# Sheet1.net
KiCad netlist of a schematic drawn in Altium Designer
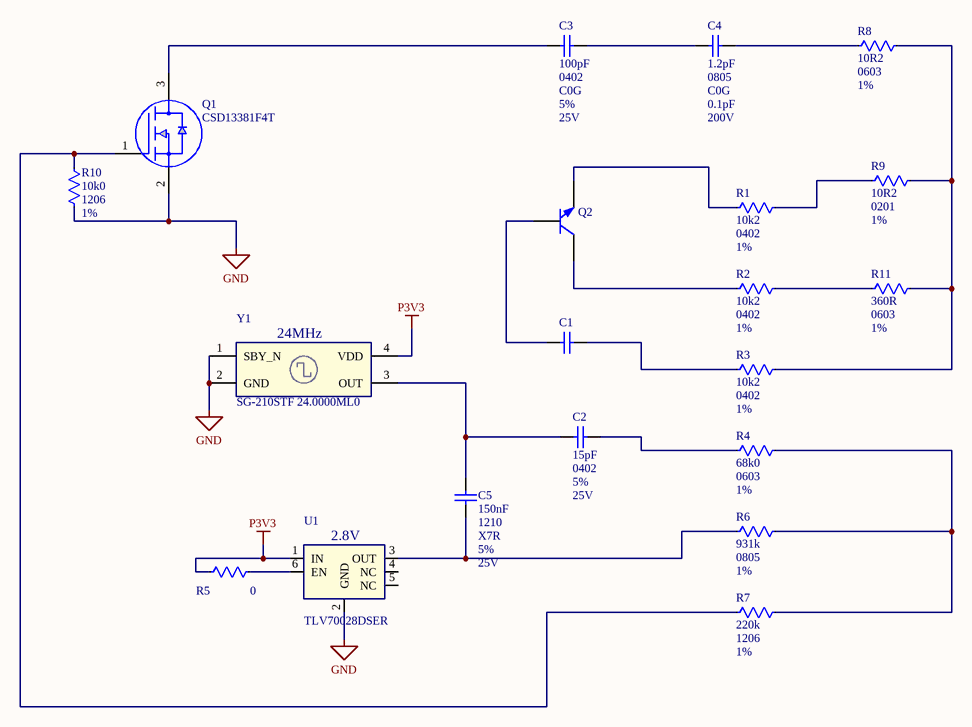
[diagram p0: Sheet1.SchDoc]

(export (version "E")
  (design (tool "Eeschema 10.0.6"))
  (components
    (comp (ref "C1")
      (value "100pF")
      (footprint "CAPC_0201(0603)_P33_N")
      (fields
        (field (name "MFR PART NUMBER") "C0201C101J3GACTU")
        (field (name "MANUFACTURER") "KEMET")
        (field (name "TOLERANCE") "±5%")
        (field (name "CREATED BY") "KristinPollock")
        (field (name "CHECKED BY") "KristinPollock")
        (field (name "UPDATED BY") "KristinPollock")
      )
      (libsource (lib "Parts") (part "CAP"))
    )
    (comp (ref "C2")
      (value "15pF")
      (footprint "CAPC_0402(1005)_P55_N")
      (description "Cap, Cer, 15pF, 5%, 25V, 0402, C0G")
      (fields
        (field (name "PACKAGE_CASE") "0402")
        (field (name "TOLERANCE") "5%")
        (field (name "VOLTAGE_RATING") "25V")
        (field (name "MFR PART NUMBER") "04023A150JAT")
        (field (name "MANUFACTURER") "AVX")
        (field (name "CREATED BY") "DJH Script")
        (field (name "CHECKED BY") "DJH Script")
      )
      (libsource (lib "passives") (part "CAPDB"))
    )
    (comp (ref "C3")
      (value "100pF")
      (footprint "CAPC_0402(1005)_P55_N")
      (description "Cap, Cer, 100pF, 5%, 25V, 0402, C0G")
      (fields
        (field (name "PACKAGE_CASE") "0402")
        (field (name "DIELECTRIC") "C0G")
        (field (name "TOLERANCE") "5%")
        (field (name "VOLTAGE_RATING") "25V")
        (field (name "MFR PART NUMBER") "04023A101JAT")
        (field (name "MANUFACTURER") "AVX")
        (field (name "CREATED BY") "DJH Script")
        (field (name "CHECKED BY") "DJH Script")
      )
      (libsource (lib "passives") (part "CAPDB"))
    )
    (comp (ref "C4")
      (value "1.2pF")
      (footprint "CAPC_0805(2012)_P95_N")
      (description "Cap, Cer, 1.2pF, 0.1pF, 200V, 0805, C0G")
      (fields
        (field (name "PACKAGE_CASE") "0805")
        (field (name "DIELECTRIC") "C0G")
        (field (name "TOLERANCE") "0.1pF")
        (field (name "VOLTAGE_RATING") "200V")
        (field (name "MFR PART NUMBER") "08052A1R2BAT")
        (field (name "MANUFACTURER") "AVX")
        (field (name "CREATED BY") "DJH Script")
        (field (name "CHECKED BY") "DJH Script")
      )
      (libsource (lib "passives") (part "CAPDB"))
    )
    (comp (ref "C5")
      (value "150nF")
      (footprint "CAPC_1210(3225)_P9_L")
      (description "Cap, Cer, 150nF, 5%, 25V, 1210, X7R")
      (fields
        (field (name "PACKAGE_CASE") "1210")
        (field (name "DIELECTRIC") "X7R")
        (field (name "TOLERANCE") "5%")
        (field (name "VOLTAGE_RATING") "25V")
        (field (name "MFR PART NUMBER") "12103C154JAT")
        (field (name "MANUFACTURER") "AVX")
        (field (name "CREATED BY") "DJH Script")
        (field (name "CHECKED BY") "DJH Script")
      )
      (libsource (lib "passives") (part "CAPDB"))
    )
    (comp (ref "Q1")
      (value "CSD13381F4T")
      (footprint "MOSFET3_TI_CSD13381F4T")
      (description "MOSFET N-CH 12V 2.1A 3PICOSTAR")
      (fields
        (field (name "MFG") "TI")
        (field (name "MANUFACTURER") "Texas Instruments")
        (field (name "CREATED BY") "Kristin Pollock")
        (field (name "CHECKED BY") "Kristin Pollock")
        (field (name "UPDATED BY") "Kristin Pollock")
      )
      (libsource (lib "Parts") (part "FET N-CH CSD13381F4T"))
    )
    (comp (ref "Q2")
      (value "MMBT3904-7-F")
      (footprint "SOT-23")
      (description "NPN General Purpose Amplifier")
      (fields
        (field (name "MFG") "Diodes Inc")
        (field (name "MANUFACTURER") "Diodes Incorporated")
        (field (name "CREATED BY") "DaveHough")
        (field (name "CHECKED BY") "DaveHough")
        (field (name "UPDATED BY") "DaveHough")
      )
      (libsource (lib "Parts") (part "MMBT3904-7-F"))
    )
    (comp (ref "R1")
      (value "10k2")
      (footprint "RESC_0402(1005)_P4_N")
      (description "Res 0402 1% 10k2 1/16W")
      (fields
        (field (name "PACKAGE_CASE") "0402")
        (field (name "TOLERANCE") "1%")
        (field (name "MFR PART NUMBER") "ERJ2RKF1022X")
        (field (name "MANUFACTURER") "Panasonic")
        (field (name "CREATED BY") "DJH Script")
        (field (name "CHECKED BY") "DJH Script")
      )
      (libsource (lib "passives") (part "RES"))
    )
    (comp (ref "R2")
      (value "10k2")
      (footprint "RESC_0402(1005)_P4_N")
      (description "Res 0402 1% 10k2 1/16W")
      (fields
        (field (name "PACKAGE_CASE") "0402")
        (field (name "TOLERANCE") "1%")
        (field (name "MFR PART NUMBER") "ERJ2RKF1022X")
        (field (name "MANUFACTURER") "Panasonic")
        (field (name "CREATED BY") "DJH Script")
        (field (name "CHECKED BY") "DJH Script")
      )
      (libsource (lib "passives") (part "RES"))
    )
    (comp (ref "R3")
      (value "10k2")
      (footprint "RESC_0402(1005)_P4_N")
      (description "Res 0402 1% 10k2 1/16W")
      (fields
        (field (name "PACKAGE_CASE") "0402")
        (field (name "TOLERANCE") "1%")
        (field (name "MFR PART NUMBER") "ERJ2RKF1022X")
        (field (name "MANUFACTURER") "Panasonic")
        (field (name "CREATED BY") "DJH Script")
        (field (name "CHECKED BY") "DJH Script")
      )
      (libsource (lib "passives") (part "RES"))
    )
    (comp (ref "R4")
      (value "68k0")
      (footprint "RESC_0603(1608)_P55_N")
      (description "Res 0603 1% 68k0 1/10W")
      (fields
        (field (name "PACKAGE_CASE") "0603")
        (field (name "TOLERANCE") "1%")
        (field (name "MFR PART NUMBER") "ERJ3EKF6802V")
        (field (name "MANUFACTURER") "Panasonic")
        (field (name "CREATED BY") "DJH Script")
        (field (name "CHECKED BY") "DJH Script")
      )
      (libsource (lib "passives") (part "RES"))
    )
    (comp (ref "R5")
      (value "0")
      (footprint "RESC_0603(1608)_P55_N")
      (fields
        (field (name "MFR PART NUMBER") "RC0603JR-070RL")
        (field (name "MANUFACTURER") "Yageo")
        (field (name "TOLERANCE") "Jumper")
        (field (name "CREATED BY") "Kristin Pollock")
        (field (name "CHECKED BY") "Kristin Pollock")
        (field (name "UPDATED BY") "KristinPollock")
      )
      (libsource (lib "Parts") (part "RES"))
    )
    (comp (ref "R6")
      (value "931k")
      (footprint "RESC_0805(2012)_P6_N")
      (description "Res 0805 1% 931k 1/8W")
      (fields
        (field (name "PACKAGE_CASE") "0805")
        (field (name "TOLERANCE") "1%")
        (field (name "MFR PART NUMBER") "ERJ6ENF9313V")
        (field (name "MANUFACTURER") "Panasonic")
        (field (name "CREATED BY") "DJH Script")
        (field (name "CHECKED BY") "DJH Script")
      )
      (libsource (lib "passives") (part "RES"))
    )
    (comp (ref "R7")
      (value "220k")
      (footprint "RESC_1206(3216)_P6_N")
      (description "Res 1206 1% 220k 1/4W")
      (fields
        (field (name "PACKAGE_CASE") "1206")
        (field (name "TOLERANCE") "1%")
        (field (name "MFR PART NUMBER") "ERJ8ENF2203V")
        (field (name "MANUFACTURER") "Panasonic")
        (field (name "CREATED BY") "DJH Script")
        (field (name "CHECKED BY") "DJH Script")
      )
      (libsource (lib "passives") (part "RES"))
    )
    (comp (ref "R8")
      (value "10R2")
      (footprint "RESC_0603(1608)_P55_N")
      (description "Res 0603 1% 10R2 1/10W")
      (fields
        (field (name "PACKAGE_CASE") "0603")
        (field (name "TOLERANCE") "1%")
        (field (name "MFR PART NUMBER") "ERJ3EKF10R2V")
        (field (name "MANUFACTURER") "Panasonic")
        (field (name "CREATED BY") "DJH Script")
        (field (name "CHECKED BY") "DJH Script")
      )
      (libsource (lib "passives") (part "RES"))
    )
    (comp (ref "R9")
      (value "10R2")
      (footprint "RESC_0201(0603)_P28_N")
      (description "Res 0201 1% 10R2 1/20W")
      (fields
        (field (name "PACKAGE_CASE") "0201")
        (field (name "TOLERANCE") "1%")
        (field (name "MFR PART NUMBER") "ERJ1GNF10R2C")
        (field (name "MANUFACTURER") "Panasonic")
        (field (name "CREATED BY") "DJH Script")
        (field (name "CHECKED BY") "DJH Script")
      )
      (libsource (lib "passives") (part "RES"))
    )
    (comp (ref "R10")
      (value "10k0")
      (footprint "RESC_1206(3216)_P6_N")
      (description "Res 1206 1% 10k0 1/4W")
      (fields
        (field (name "PACKAGE_CASE") "1206")
        (field (name "TOLERANCE") "1%")
        (field (name "MFR PART NUMBER") "ERJ8ENF1002V")
        (field (name "MANUFACTURER") "Panasonic")
        (field (name "CREATED BY") "DJH Script")
        (field (name "CHECKED BY") "DJH Script")
      )
      (libsource (lib "passives") (part "RES"))
    )
    (comp (ref "R11")
      (value "360R")
      (footprint "RESC_0603(1608)_P55_N")
      (description "Res 0603 1% 360R 1/10W")
      (fields
        (field (name "PACKAGE_CASE") "0603")
        (field (name "TOLERANCE") "1%")
        (field (name "MFR PART NUMBER") "ERJ3EKF3600V")
        (field (name "MANUFACTURER") "Panasonic")
        (field (name "CREATED BY") "DJH Script")
        (field (name "CHECKED BY") "DJH Script")
      )
      (libsource (lib "passives") (part "RES"))
    )
    (comp (ref "U1")
      (value "TLV70028DSER")
      (footprint "TI DSE S-PWSON-N6")
      (description "IC REG LDO 2.8V 0.2A 6WSON")
      (fields
        (field (name "MFG") "TI")
        (field (name "MANUFACTURER") "Texas Instruments")
        (field (name "CREATED BY") "Kristin Pollock")
        (field (name "CHECKED BY") "Kristin Pollock")
        (field (name "UPDATED BY") "Kristin Pollock")
      )
      (libsource (lib "Parts") (part "TLV70028DSER"))
    )
    (comp (ref "Y1")
      (value "SG-210STF 24.0000ML0")
      (footprint "Epson SG-210STF")
      (description "OSC XO 24.000MHZ CMOS SMD")
      (fields
        (field (name "MFG") "Abracon")
        (field (name "MANUFACTURER") "EPSON")
        (field (name "CREATED BY") "Kristin Pollock")
        (field (name "CHECKED BY") "Kristin Pollock")
        (field (name "UPDATED BY") "Kristin Pollock")
      )
      (libsource (lib "Parts") (part "SG-210STF 24.0000ML0"))
    )
  )
  (nets
    (net (code "1") (name "GND") (class "Default")
      (node (ref "Q1") (pin "2") (pinfunction "S_2") (pintype "passive"))
      (node (ref "R10") (pin "2") (pintype "passive"))
      (node (ref "U1") (pin "2") (pinfunction "GND_2") (pintype "passive"))
      (node (ref "Y1") (pin "1") (pinfunction "SBY_N_1") (pintype "passive"))
      (node (ref "Y1") (pin "2") (pinfunction "GND_2") (pintype "passive"))
    )
    (net (code "2") (name "Net-(C1-Pad2)") (class "Default")
      (node (ref "C1") (pin "2") (pinfunction "2_2") (pintype "passive"))
      (node (ref "R3") (pin "2") (pintype "passive"))
    )
    (net (code "3") (name "Net-(C2-Pad2)") (class "Default")
      (node (ref "C2") (pin "2") (pinfunction "2_2") (pintype "passive"))
      (node (ref "R4") (pin "2") (pintype "passive"))
    )
    (net (code "4") (name "Net-(C3-Pad2)") (class "Default")
      (node (ref "C3") (pin "2") (pinfunction "2_2") (pintype "passive"))
      (node (ref "C4") (pin "1") (pinfunction "1_1") (pintype "passive"))
    )
    (net (code "5") (name "Net-(C4-Pad2)") (class "Default")
      (node (ref "C4") (pin "2") (pinfunction "2_2") (pintype "passive"))
      (node (ref "R8") (pin "2") (pintype "passive"))
    )
    (net (code "6") (name "Net-(Q1-D)") (class "Default")
      (node (ref "C3") (pin "1") (pinfunction "1_1") (pintype "passive"))
      (node (ref "Q1") (pin "3") (pinfunction "D_3") (pintype "passive"))
    )
    (net (code "7") (name "Net-(Q1-G)") (class "Default")
      (node (ref "Q1") (pin "1") (pinfunction "G_1") (pintype "passive"))
      (node (ref "R10") (pin "1") (pintype "passive"))
      (node (ref "R7") (pin "2") (pintype "passive"))
    )
    (net (code "8") (name "Net-(Q2-B)") (class "Default")
      (node (ref "C1") (pin "1") (pinfunction "1_1") (pintype "passive"))
      (node (ref "Q2") (pin "2") (pinfunction "B_2") (pintype "passive"))
    )
    (net (code "9") (name "Net-(Q2-C)") (class "Default")
      (node (ref "Q2") (pin "3") (pinfunction "C_3") (pintype "passive"))
      (node (ref "R2") (pin "2") (pintype "passive"))
    )
    (net (code "10") (name "Net-(Q2-E)") (class "Default")
      (node (ref "Q2") (pin "1") (pinfunction "E_1") (pintype "passive"))
      (node (ref "R1") (pin "2") (pintype "passive"))
    )
    (net (code "11") (name "Net-(R1-Pad1)") (class "Default")
      (node (ref "R1") (pin "1") (pintype "passive"))
      (node (ref "R9") (pin "2") (pintype "passive"))
    )
    (net (code "12") (name "Net-(R4-Pad1)") (class "Default")
      (node (ref "R4") (pin "1") (pintype "passive"))
      (node (ref "R6") (pin "1") (pintype "passive"))
      (node (ref "R7") (pin "1") (pintype "passive"))
    )
    (net (code "13") (name "Net-(R11-Pad1)") (class "Default")
      (node (ref "R11") (pin "1") (pintype "passive"))
      (node (ref "R3") (pin "1") (pintype "passive"))
      (node (ref "R8") (pin "1") (pintype "passive"))
      (node (ref "R9") (pin "1") (pintype "passive"))
    )
    (net (code "14") (name "Net-(R11-Pad2)") (class "Default")
      (node (ref "R11") (pin "2") (pintype "passive"))
      (node (ref "R2") (pin "1") (pintype "passive"))
    )
    (net (code "15") (name "Net-(U1-EN)") (class "Default")
      (node (ref "R5") (pin "1") (pintype "passive"))
      (node (ref "U1") (pin "6") (pinfunction "EN_6") (pintype "passive"))
    )
    (net (code "16") (name "Net-(U1-OUT)") (class "Default")
      (node (ref "C5") (pin "1") (pinfunction "1_1") (pintype "passive"))
      (node (ref "R6") (pin "2") (pintype "passive"))
      (node (ref "U1") (pin "3") (pinfunction "OUT_3") (pintype "passive"))
    )
    (net (code "17") (name "Net-(Y1-OUT)") (class "Default")
      (node (ref "C2") (pin "1") (pinfunction "1_1") (pintype "passive"))
      (node (ref "C5") (pin "2") (pinfunction "2_2") (pintype "passive"))
      (node (ref "Y1") (pin "3") (pinfunction "OUT_3") (pintype "passive"))
    )
    (net (code "18") (name "P3V3") (class "Default")
      (node (ref "R5") (pin "2") (pintype "passive"))
      (node (ref "U1") (pin "1") (pinfunction "IN_1") (pintype "passive"))
      (node (ref "Y1") (pin "4") (pinfunction "VDD_4") (pintype "passive"))
    )
    (net (code "19") (name "unconnected-(U1-NC-Pad4)") (class "Default")
      (node (ref "U1") (pin "4") (pinfunction "NC_4") (pintype "passive"))
    )
    (net (code "20") (name "unconnected-(U1-NC-Pad5)") (class "Default")
      (node (ref "U1") (pin "5") (pinfunction "NC_5") (pintype "passive"))
    )
  )
)
